# Power_Distribution_-_Parking_Brake_Actua.net
KiCad netlist of a schematic drawn in Altium Designer
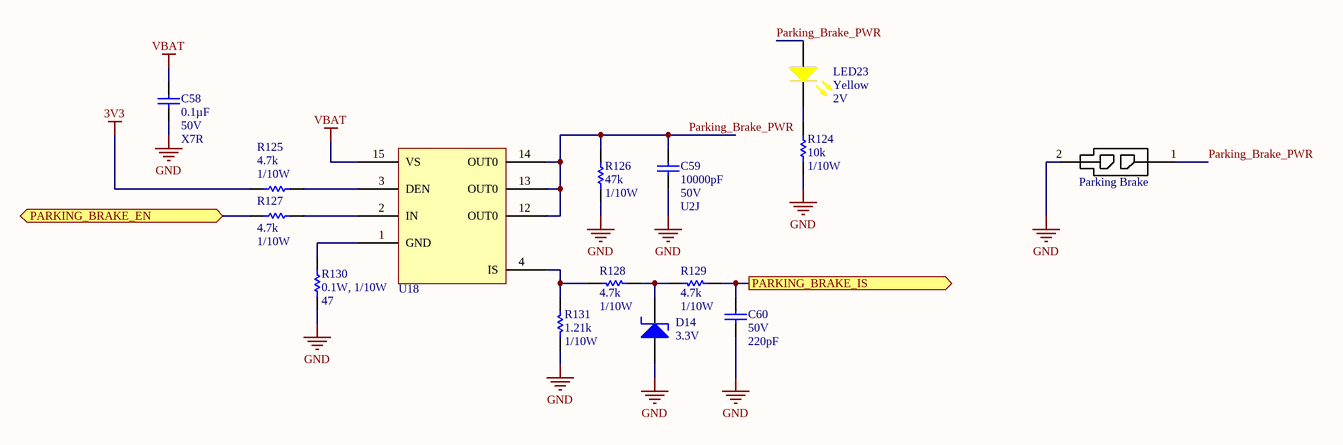
[diagram p0: Power Distribution - Parking Brake Actuator.SchDoc]

(export (version "E")
  (design (tool "Eeschema 10.0.6"))
  (components
    (comp (ref "C58")
      (value "CAP CER 0.1UF 50V 10% X7R 0603")
      (footprint "CAP, 0603")
      (description "0.10µF ±10% 50V Ceramic Capacitor X7R 0603 (1608 Metric)")
      (fields
        (field (name "TOLERANCE") "±10%")
        (field (name "CAPACITANCE") "0.1µF")
        (field (name "VOLTAGE") "50V")
        (field (name "TEMPERATURE COEFFICIENT") "X7R")
      )
      (libsource (lib "Schematic Diagrams") (part "CAP CER 0.1UF 50V 10% X7R 0603"))
    )
    (comp (ref "C59")
      (value "CAP CER 10nF 50V 5% X7R 0603")
      (footprint "CAP, 0603")
      (description "10000pF ±5% 50V Ceramic Capacitor U2J 0603 (1608 Metric)")
      (fields
        (field (name "TOLERANCE") "±5%")
        (field (name "CAPACITANCE") "10000pF")
        (field (name "VOLTAGE") "50V")
        (field (name "TEMPERATURE COEFFICIENT") "U2J")
      )
      (libsource (lib "Schematic Diagrams") (part "CAP CER 10nF 50V 5% X7R 0603"))
    )
    (comp (ref "C60")
      (value "CAP CER 220PF 50V C0G/NP0 0603")
      (footprint "CAP, 0603")
      (description "220pF ±5% 50V Ceramic Capacitor C0G, NP0 0603 (1608 Metric)")
      (fields
        (field (name "MANUFACTURER") "KEMET")
        (field (name "TOLERANCE") "5%")
        (field (name "VOLTAGE RATING") "50V")
        (field (name "CAPACITANCE") "220pF")
      )
      (libsource (lib "Schematic Diagrams") (part "CAP CER 220PF 50V C0G/NP0 0603"))
    )
    (comp (ref "D14")
      (value "DIODE ZENER 3.3V 200MW SOD323")
      (footprint "sod-323")
      (description "Zener Diode 3.3V 200mW ±5% Surface Mount SOD-323")
      (fields (field (name "VOLTAGE") "3.3V"))
      (libsource (lib "Schematic Diagrams") (part "DIODE ZENER 3.3V 200MW SOD323"))
    )
    (comp (ref "LED23")
      (value "LED YELLOW CLEAR 2.1V 0603")
      (footprint "LED_0603")
      (description "Yellow 590nm LED Indication - Discrete 2V 0603 (1608 Metric)")
      (fields
        (field (name "MANUFACTURER") "Wurth Electronics Inc.")
        (field (name "MANUFACTURER PART NUMBER") "150060YS75000")
        (field (name "COLOR") "Yellow")
        (field (name "VOLTAGE - FORWARD (VF) (TYP)") "2V")
      )
      (libsource (lib "Schematic Diagrams") (part "LED YELLOW CLEAR 2.1V 0603"))
    )
    (comp (ref "Parking Brake")
      (value "CONN 2POS MICRO-FIT 3mm")
      (footprint "CONN, 2POS MICRO-FIT")
      (description "Connector Header Through Hole 2 position")
      (fields (field (name "MANUFACTURER") "Molex") (field (name "MANUFACTURER PART NUMBER") "43045-0227"))
      (libsource (lib "Schematic Diagrams") (part "CONN 2POS MICRO-FIT 3mm"))
    )
    (comp (ref "R124")
      (value "RES 10K OHM 1% 1/10W 0603")
      (footprint "RES, 0603")
      (description "RES SMD 10K OHM 1% 1/10W 0603")
      (fields
        (field (name "TOLERANCE") "±1%")
        (field (name "RESISTANCE") "10k")
        (field (name "POWER") "1/10W")
      )
      (libsource (lib "Schematic Diagrams") (part "RES 10K OHM 1% 1/10W 0603"))
    )
    (comp (ref "R125")
      (value "RES 4.7K OHM 1% 1/10W 0603")
      (footprint "RES, 0603")
      (description "4.7k Ohm ±1% 0.1W, 1/10W Chip Resistor 0603 (1608 Metric) Moisture Resistant Thick Film")
      (fields
        (field (name "TOLERANCE") "±1%")
        (field (name "RESISTANCE (OHMS)") "4.7k")
        (field (name "POWER (WATTS)") "1/10W")
      )
      (libsource (lib "Schematic Diagrams") (part "RES 4.7K OHM 1% 1/10W 0603"))
    )
    (comp (ref "R126")
      (value "RES 47K OHM 1% 1/10W 0603")
      (footprint "RES, 0603")
      (description "47 kOhms ±1% 0.1W, 1/10W Chip Resistor 0603 (1608 Metric) Automotive AEC-Q200 Thick Film")
      (fields
        (field (name "MANUFACTURER") "Panasonic")
        (field (name "MANUFACTURER PART NUMBER") "ERJ3EKF4702V")
        (field (name "RESISTANCE") "47k")
        (field (name "POWER RATING") "1/10W")
      )
      (libsource (lib "Schematic Diagrams") (part "RES 47K OHM 1% 1/10W 0603"))
    )
    (comp (ref "R127")
      (value "RES 4.7K OHM 1% 1/10W 0603")
      (footprint "RES, 0603")
      (description "4.7k Ohm ±1% 0.1W, 1/10W Chip Resistor 0603 (1608 Metric) Moisture Resistant Thick Film")
      (fields
        (field (name "TOLERANCE") "±1%")
        (field (name "RESISTANCE (OHMS)") "4.7k")
        (field (name "POWER (WATTS)") "1/10W")
      )
      (libsource (lib "Schematic Diagrams") (part "RES 4.7K OHM 1% 1/10W 0603"))
    )
    (comp (ref "R128")
      (value "RES 4.7K OHM 1% 1/10W 0603")
      (footprint "RES, 0603")
      (description "4.7k Ohm ±1% 0.1W, 1/10W Chip Resistor 0603 (1608 Metric) Moisture Resistant Thick Film")
      (fields
        (field (name "TOLERANCE") "±1%")
        (field (name "RESISTANCE (OHMS)") "4.7k")
        (field (name "POWER (WATTS)") "1/10W")
      )
      (libsource (lib "Schematic Diagrams") (part "RES 4.7K OHM 1% 1/10W 0603"))
    )
    (comp (ref "R129")
      (value "RES 4.7K OHM 1% 1/10W 0603")
      (footprint "RES, 0603")
      (description "4.7k Ohm ±1% 0.1W, 1/10W Chip Resistor 0603 (1608 Metric) Moisture Resistant Thick Film")
      (fields
        (field (name "TOLERANCE") "±1%")
        (field (name "RESISTANCE (OHMS)") "4.7k")
        (field (name "POWER (WATTS)") "1/10W")
      )
      (libsource (lib "Schematic Diagrams") (part "RES 4.7K OHM 1% 1/10W 0603"))
    )
    (comp (ref "R130")
      (value "RES SMD 47 OHM 1% 1/10W 0603")
      (footprint "RES, 0603")
      (fields
        (field (name "TOLERANCE") "±1%")
        (field (name "POWER (WATTS)") "0.1W, 1/10W")
        (field (name "VALUES") "47")
      )
      (libsource (lib "Schematic Diagrams") (part "RES SMD 47 OHM 1% 1/10W 0603"))
    )
    (comp (ref "R131")
      (value "RES 1.21K OHM 1% 1/10W 0603")
      (footprint "RES, 0603")
      (description "1.21k Ohm ±1% 0.1W, 1/10W Chip Resistor 0603 (1608 Metric) Moisture Resistant Thick Film")
      (fields
        (field (name "TOLERANCE") "±1%")
        (field (name "RESISTANCE") "1.21k")
        (field (name "POWER") "1/10W")
      )
      (libsource (lib "Schematic Diagrams") (part "RES 1.21K OHM 1% 1/10W 0603"))
    )
    (comp (ref "U18")
      (value "IC LOAD SWITCH BTS70401EPA PG-TSDSO-14-22")
      (footprint "IC LOAD SWITCH PG-TSDSO-14-22")
      (description "Power Switch/Driver 1:1 N-Channel 4.5A PG-TSDSO-14-22")
      (fields
        (field (name "MANUFACTURER") "Infineon")
        (field (name "MANUFACTURER PART NUMBER") "BTS70401EPAXUMA1")
      )
      (libsource (lib "Schematic Diagrams") (part "IC LOAD SWITCH BTS70401EPA PG-TSDSO-14-22"))
    )
  )
  (nets
    (net (code "1") (name "/PARKING_BRAKE_EN") (class "Default")
      (node (ref "R127") (pin "1") (pinfunction "1_1") (pintype "passive"))
    )
    (net (code "2") (name "/PARKING_BRAKE_IS") (class "Default")
      (node (ref "C60") (pin "1") (pinfunction "1_1") (pintype "passive"))
      (node (ref "R129") (pin "1") (pinfunction "1_1") (pintype "passive"))
    )
    (net (code "3") (name "/Parking_Brake_PWR") (class "Default")
      (node (ref "C59") (pin "1") (pinfunction "1_1") (pintype "passive"))
      (node (ref "LED23") (pin "1") (pinfunction "A_1") (pintype "passive"))
      (node (ref "Parking Brake") (pin "1") (pinfunction "1_1") (pintype "passive"))
      (node (ref "R126") (pin "1") (pinfunction "1_1") (pintype "passive"))
      (node (ref "U18") (pin "12") (pinfunction "OUT0_12") (pintype "passive"))
      (node (ref "U18") (pin "13") (pinfunction "OUT0_13") (pintype "passive"))
      (node (ref "U18") (pin "14") (pinfunction "OUT0_14") (pintype "passive"))
    )
    (net (code "4") (name "3V3") (class "Default")
      (node (ref "R125") (pin "1") (pinfunction "1_1") (pintype "passive"))
    )
    (net (code "5") (name "GND") (class "Default")
      (node (ref "C58") (pin "2") (pinfunction "2_2") (pintype "passive"))
      (node (ref "C59") (pin "2") (pinfunction "2_2") (pintype "passive"))
      (node (ref "C60") (pin "2") (pinfunction "2_2") (pintype "passive"))
      (node (ref "D14") (pin "1") (pinfunction "A_1") (pintype "passive"))
      (node (ref "Parking Brake") (pin "2") (pinfunction "2_2") (pintype "passive"))
      (node (ref "R124") (pin "2") (pinfunction "2_2") (pintype "passive"))
      (node (ref "R126") (pin "2") (pinfunction "2_2") (pintype "passive"))
      (node (ref "R130") (pin "2") (pinfunction "2_2") (pintype "passive"))
      (node (ref "R131") (pin "2") (pinfunction "2_2") (pintype "passive"))
    )
    (net (code "6") (name "Net-(D14-K)") (class "Default")
      (node (ref "D14") (pin "2") (pinfunction "K_2") (pintype "passive"))
      (node (ref "R128") (pin "1") (pinfunction "1_1") (pintype "passive"))
      (node (ref "R129") (pin "2") (pinfunction "2_2") (pintype "passive"))
    )
    (net (code "7") (name "Net-(LED23-K)") (class "Default")
      (node (ref "LED23") (pin "2") (pinfunction "K_2") (pintype "passive"))
      (node (ref "R124") (pin "1") (pinfunction "1_1") (pintype "passive"))
    )
    (net (code "8") (name "Net-(U18-DEN)") (class "Default")
      (node (ref "R125") (pin "2") (pinfunction "2_2") (pintype "passive"))
      (node (ref "U18") (pin "3") (pinfunction "DEN_3") (pintype "passive"))
    )
    (net (code "9") (name "Net-(U18-GND)") (class "Default")
      (node (ref "R130") (pin "1") (pinfunction "1_1") (pintype "passive"))
      (node (ref "U18") (pin "1") (pinfunction "GND_1") (pintype "passive"))
    )
    (net (code "10") (name "Net-(U18-IN)") (class "Default")
      (node (ref "R127") (pin "2") (pinfunction "2_2") (pintype "passive"))
      (node (ref "U18") (pin "2") (pinfunction "IN_2") (pintype "passive"))
    )
    (net (code "11") (name "Net-(U18-IS)") (class "Default")
      (node (ref "R128") (pin "2") (pinfunction "2_2") (pintype "passive"))
      (node (ref "R131") (pin "1") (pinfunction "1_1") (pintype "passive"))
      (node (ref "U18") (pin "4") (pinfunction "IS_4") (pintype "passive"))
    )
    (net (code "12") (name "VBAT") (class "Default")
      (node (ref "C58") (pin "1") (pinfunction "1_1") (pintype "passive"))
      (node (ref "U18") (pin "15") (pinfunction "VS_15") (pintype "passive"))
    )
  )
)
